# MotorDriverSchem.net
KiCad netlist of a schematic drawn in EAGLE
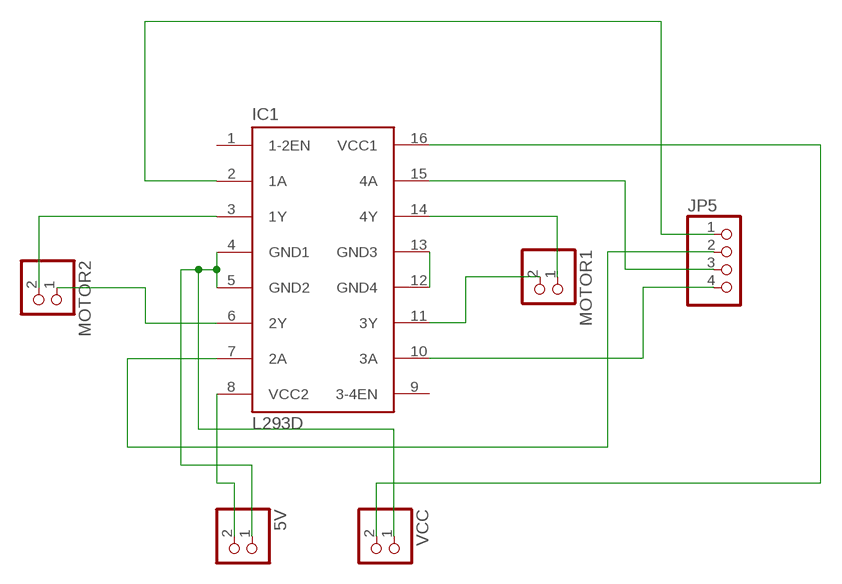
[diagram p0: schematic, sheet 1]

(export (version "E")
  (design (tool "Eeschema 10.0.6"))
  (components
    (comp (ref "5V")
      (value "PINHD-1X2")
      (footprint "eagle-import:1X02")
      (libsource (lib "eagle-import") (part "PINHD-1X2"))
    )
    (comp (ref "IC1")
      (value "L293D")
      (footprint "eagle-import:DIL16")
      (libsource (lib "eagle-import") (part "L293D"))
    )
    (comp (ref "JP5")
      (value "PINHD-1X4")
      (footprint "eagle-import:1X04")
      (libsource (lib "eagle-import") (part "PINHD-1X4"))
    )
    (comp (ref "MOTOR1")
      (value "PINHD-1X2")
      (footprint "eagle-import:1X02")
      (libsource (lib "eagle-import") (part "PINHD-1X2"))
    )
    (comp (ref "MOTOR2")
      (value "PINHD-1X2")
      (footprint "eagle-import:1X02")
      (libsource (lib "eagle-import") (part "PINHD-1X2"))
    )
    (comp (ref "VCC")
      (value "PINHD-1X2")
      (footprint "eagle-import:1X02")
      (libsource (lib "eagle-import") (part "PINHD-1X2"))
    )
  )
  (nets
    (net (code "1") (name "Net-(IC1-1A)") (class "Default")
      (node (ref "IC1") (pin "2") (pinfunction "1A_2") (pintype "input"))
      (node (ref "JP5") (pin "1") (pinfunction "1_1") (pintype "passive"))
    )
    (net (code "2") (name "Net-(IC1-1Y)") (class "Default")
      (node (ref "IC1") (pin "3") (pinfunction "1Y_3") (pintype "output"))
      (node (ref "MOTOR2") (pin "2") (pinfunction "2_2") (pintype "passive"))
    )
    (net (code "3") (name "Net-(IC1-2A)") (class "Default")
      (node (ref "IC1") (pin "7") (pinfunction "2A_7") (pintype "input"))
      (node (ref "JP5") (pin "2") (pinfunction "2_2") (pintype "passive"))
    )
    (net (code "4") (name "Net-(IC1-2Y)") (class "Default")
      (node (ref "IC1") (pin "6") (pinfunction "2Y_6") (pintype "output"))
      (node (ref "MOTOR2") (pin "1") (pinfunction "1_1") (pintype "passive"))
    )
    (net (code "5") (name "Net-(IC1-3A)") (class "Default")
      (node (ref "IC1") (pin "10") (pinfunction "3A_10") (pintype "input"))
      (node (ref "JP5") (pin "4") (pinfunction "4_4") (pintype "passive"))
    )
    (net (code "6") (name "Net-(IC1-3Y)") (class "Default")
      (node (ref "IC1") (pin "11") (pinfunction "3Y_11") (pintype "output"))
      (node (ref "MOTOR1") (pin "2") (pinfunction "2_2") (pintype "passive"))
    )
    (net (code "7") (name "Net-(IC1-4A)") (class "Default")
      (node (ref "IC1") (pin "15") (pinfunction "4A_15") (pintype "input"))
      (node (ref "JP5") (pin "3") (pinfunction "3_3") (pintype "passive"))
    )
    (net (code "8") (name "Net-(IC1-4Y)") (class "Default")
      (node (ref "IC1") (pin "14") (pinfunction "4Y_14") (pintype "output"))
      (node (ref "MOTOR1") (pin "1") (pinfunction "1_1") (pintype "passive"))
    )
    (net (code "9") (name "Net-(IC1-GND1)") (class "Default")
      (node (ref "5V") (pin "1") (pinfunction "1_1") (pintype "passive"))
      (node (ref "IC1") (pin "4") (pinfunction "GND1_4") (pintype "power_in"))
      (node (ref "IC1") (pin "5") (pinfunction "GND2_5") (pintype "power_in"))
      (node (ref "VCC") (pin "1") (pinfunction "1_1") (pintype "passive"))
    )
    (net (code "10") (name "Net-(IC1-GND3)") (class "Default")
      (node (ref "IC1") (pin "12") (pinfunction "GND4_12") (pintype "power_in"))
      (node (ref "IC1") (pin "13") (pinfunction "GND3_13") (pintype "power_in"))
    )
    (net (code "11") (name "Net-(IC1-VCC1)") (class "Default")
      (node (ref "IC1") (pin "16") (pinfunction "VCC1_16") (pintype "power_in"))
      (node (ref "VCC") (pin "2") (pinfunction "2_2") (pintype "passive"))
    )
    (net (code "12") (name "Net-(IC1-VCC2)") (class "Default")
      (node (ref "5V") (pin "2") (pinfunction "2_2") (pintype "passive"))
      (node (ref "IC1") (pin "8") (pinfunction "VCC2_8") (pintype "power_in"))
    )
    (net (code "13") (name "unconnected-(IC1-1-2EN-Pad1)") (class "Default")
      (node (ref "IC1") (pin "1") (pinfunction "1-2EN_1") (pintype "input"))
    )
    (net (code "14") (name "unconnected-(IC1-3-4EN-Pad9)") (class "Default")
      (node (ref "IC1") (pin "9") (pinfunction "3-4EN_9") (pintype "input"))
    )
  )
)
